# standalone_mod.net
KiCad netlist of a schematic drawn in EAGLE
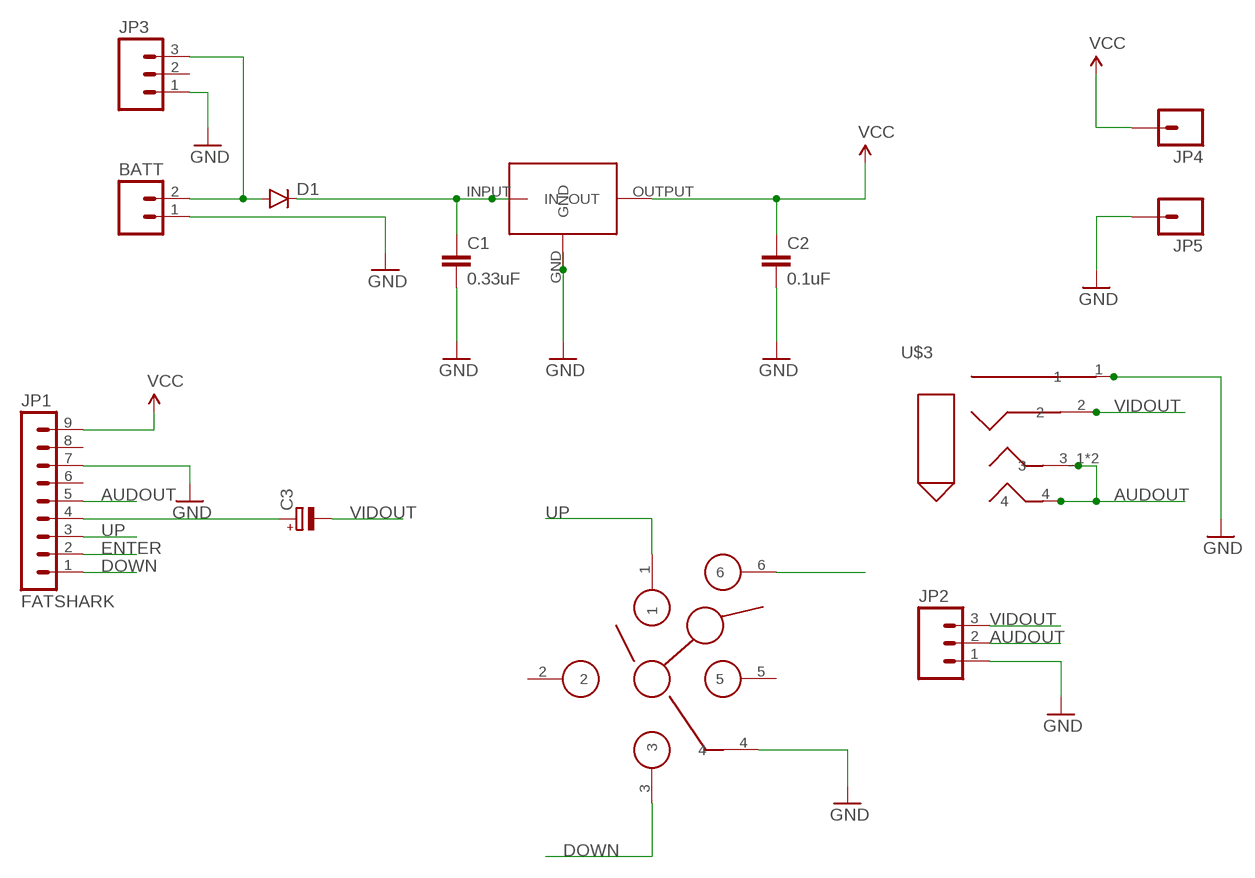
[diagram p0: schematic, sheet 1]

(export (version "E")
  (design (tool "Eeschema 10.0.6"))
  (components
    (comp (ref "BATT")
      (value "M02LOCK_LONGPADS")
      (footprint "eagle-import:1X02_LOCK_LONGPADS")
      (libsource (lib "eagle-import") (part "M02LOCK_LONGPADS"))
    )
    (comp (ref "C1")
      (value "0.33uF")
      (footprint "eagle-import:0805")
      (libsource (lib "eagle-import") (part "CAP0805"))
    )
    (comp (ref "C2")
      (value "0.1uF")
      (footprint "eagle-import:0805")
      (libsource (lib "eagle-import") (part "CAP0805"))
    )
    (comp (ref "C3")
      (value "CPOL-EUE3.5-8")
      (footprint "eagle-import:E3,5-8")
      (libsource (lib "eagle-import") (part "CPOL-EUE3.5-8"))
    )
    (comp (ref "D1")
      (value "DIODESMA")
      (footprint "eagle-import:SMA-DIODE")
      (libsource (lib "eagle-import") (part "DIODESMA"))
    )
    (comp (ref "JP1")
      (value "FATSHARK")
      (footprint "eagle-import:MA09-1")
      (libsource (lib "eagle-import") (part "MA09-1"))
    )
    (comp (ref "JP2")
      (value "M03PTH")
      (footprint "eagle-import:1X03")
      (libsource (lib "eagle-import") (part "M03PTH"))
    )
    (comp (ref "JP3")
      (value "M03LONGPADS")
      (footprint "eagle-import:1X03_LONGPADS")
      (libsource (lib "eagle-import") (part "M03LONGPADS"))
    )
    (comp (ref "JP4")
      (value "M01SMD")
      (footprint "eagle-import:LUXEON-PAD")
      (libsource (lib "eagle-import") (part "M01SMD"))
    )
    (comp (ref "JP5")
      (value "M01SMD")
      (footprint "eagle-import:LUXEON-PAD")
      (libsource (lib "eagle-import") (part "M01SMD"))
    )
    (comp (ref "U$1")
      (value "7805")
      (footprint "eagle-import:DDPAK")
      (libsource (lib "eagle-import") (part "7805"))
    )
    (comp (ref "U$2")
      (value "SKQUCAA010")
      (footprint "eagle-import:SKQUCAA010")
      (libsource (lib "eagle-import") (part "SKQUCAA010"))
    )
    (comp (ref "U$3")
      (value "MC001293JACK")
      (footprint "eagle-import:MC001293")
      (libsource (lib "eagle-import") (part "MC001293JACK"))
    )
  )
  (nets
    (net (code "1") (name "/AUDOUT") (class "Default")
      (node (ref "JP1") (pin "5") (pinfunction "5_5") (pintype "passive"))
      (node (ref "JP2") (pin "2") (pinfunction "2_2") (pintype "passive"))
      (node (ref "U$3") (pin "3_1") (pinfunction "3_3_1") (pintype "bidirectional"))
      (node (ref "U$3") (pin "3_2") (pinfunction "3_3_2") (pintype "bidirectional"))
      (node (ref "U$3") (pin "4") (pinfunction "4_4") (pintype "bidirectional"))
    )
    (net (code "2") (name "/DOWN") (class "Default")
      (node (ref "JP1") (pin "1") (pinfunction "1_1") (pintype "passive"))
      (node (ref "U$2") (pin "3") (pinfunction "3_3") (pintype "bidirectional"))
    )
    (net (code "3") (name "/ENTER") (class "Default")
      (node (ref "JP1") (pin "2") (pinfunction "2_2") (pintype "passive"))
      (node (ref "U$2") (pin "6") (pinfunction "6_6") (pintype "bidirectional"))
    )
    (net (code "4") (name "/UP") (class "Default")
      (node (ref "JP1") (pin "3") (pinfunction "3_3") (pintype "passive"))
      (node (ref "U$2") (pin "1") (pinfunction "1_1") (pintype "bidirectional"))
    )
    (net (code "5") (name "/VIDOUT") (class "Default")
      (node (ref "C3") (pin "-") (pinfunction "-_-") (pintype "passive"))
      (node (ref "JP2") (pin "3") (pinfunction "3_3") (pintype "passive"))
      (node (ref "U$3") (pin "2") (pinfunction "2_2") (pintype "bidirectional"))
    )
    (net (code "6") (name "GND") (class "Default")
      (node (ref "BATT") (pin "1") (pinfunction "1_1") (pintype "passive"))
      (node (ref "C1") (pin "2") (pinfunction "2_2") (pintype "passive"))
      (node (ref "C2") (pin "2") (pinfunction "2_2") (pintype "passive"))
      (node (ref "JP1") (pin "7") (pinfunction "7_7") (pintype "passive"))
      (node (ref "JP2") (pin "1") (pinfunction "1_1") (pintype "passive"))
      (node (ref "JP3") (pin "1") (pinfunction "1_1") (pintype "passive"))
      (node (ref "JP5") (pin "P$1") (pinfunction "1_P$1") (pintype "passive"))
      (node (ref "U$1") (pin "GND") (pinfunction "GND_GND") (pintype "bidirectional"))
      (node (ref "U$2") (pin "4") (pinfunction "4_4") (pintype "bidirectional"))
      (node (ref "U$3") (pin "1") (pinfunction "1_1") (pintype "bidirectional"))
    )
    (net (code "7") (name "Net-(BATT-Pad2)") (class "Default")
      (node (ref "BATT") (pin "2") (pinfunction "2_2") (pintype "passive"))
      (node (ref "D1") (pin "A") (pinfunction "A_A") (pintype "passive"))
      (node (ref "JP3") (pin "3") (pinfunction "3_3") (pintype "passive"))
    )
    (net (code "8") (name "Net-(C3-Pad+)") (class "Default")
      (node (ref "C3") (pin "+") (pinfunction "+_+") (pintype "passive"))
      (node (ref "JP1") (pin "4") (pinfunction "4_4") (pintype "passive"))
    )
    (net (code "9") (name "Net-(U$1-IN)") (class "Default")
      (node (ref "C1") (pin "1") (pinfunction "1_1") (pintype "passive"))
      (node (ref "D1") (pin "C") (pinfunction "C_C") (pintype "passive"))
      (node (ref "U$1") (pin "INPUT") (pinfunction "IN_INPUT") (pintype "bidirectional"))
    )
    (net (code "10") (name "VCC") (class "Default")
      (node (ref "C2") (pin "1") (pinfunction "1_1") (pintype "passive"))
      (node (ref "JP1") (pin "9") (pinfunction "9_9") (pintype "passive"))
      (node (ref "JP4") (pin "P$1") (pinfunction "1_P$1") (pintype "passive"))
      (node (ref "U$1") (pin "OUTPUT") (pinfunction "OUT_OUTPUT") (pintype "bidirectional"))
    )
    (net (code "11") (name "unconnected-(JP1-Pad6)") (class "Default")
      (node (ref "JP1") (pin "6") (pinfunction "6_6") (pintype "passive"))
    )
    (net (code "12") (name "unconnected-(JP1-Pad8)") (class "Default")
      (node (ref "JP1") (pin "8") (pinfunction "8_8") (pintype "passive"))
    )
    (net (code "13") (name "unconnected-(JP3-Pad2)") (class "Default")
      (node (ref "JP3") (pin "2") (pinfunction "2_2") (pintype "passive"))
    )
    (net (code "14") (name "unconnected-(U$2-Pad2)") (class "Default")
      (node (ref "U$2") (pin "2") (pinfunction "2_2") (pintype "bidirectional"))
    )
    (net (code "15") (name "unconnected-(U$2-Pad5)") (class "Default")
      (node (ref "U$2") (pin "5") (pinfunction "5_5") (pintype "bidirectional"))
    )
  )
)
